# RS232.net
KiCad netlist of a schematic drawn in EAGLE
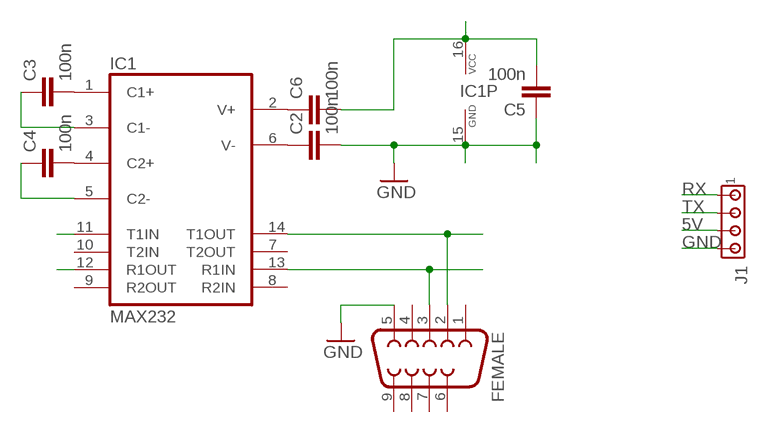
[diagram p0: schematic, sheet 1]

(export (version "E")
  (design (tool "Eeschema 10.0.6"))
  (components
    (comp (ref "C2")
      (value "100n")
      (footprint "eagle-import:C0805")
      (libsource (lib "eagle-import") (part "C-EUC0805"))
    )
    (comp (ref "C3")
      (value "100n")
      (footprint "eagle-import:C0805")
      (libsource (lib "eagle-import") (part "C-EUC0805"))
    )
    (comp (ref "C4")
      (value "100n")
      (footprint "eagle-import:C0805")
      (libsource (lib "eagle-import") (part "C-EUC0805"))
    )
    (comp (ref "C5")
      (value "100n")
      (footprint "eagle-import:C0805")
      (libsource (lib "eagle-import") (part "C-EUC0805"))
    )
    (comp (ref "C6")
      (value "100n")
      (footprint "eagle-import:C0805")
      (libsource (lib "eagle-import") (part "C-EUC0805"))
    )
    (comp (ref "FEMALE")
      (value "F09H")
      (footprint "eagle-import:F09H")
      (libsource (lib "eagle-import") (part "F09H"))
    )
    (comp (ref "IC1")
      (value "MAX232")
      (footprint "eagle-import:SO16")
      (libsource (lib "eagle-import") (part "MAX232ECWES"))
    )
    (comp (ref "J1")
      (value "MTA04-156")
      (footprint "eagle-import:1X4MTA")
      (libsource (lib "eagle-import") (part "MTA04-156"))
    )
  )
  (nets
    (net (code "1") (name "/5V") (class "Default")
      (node (ref "C5") (pin "2") (pinfunction "2_2") (pintype "passive"))
      (node (ref "C6") (pin "2") (pinfunction "2_2") (pintype "passive"))
      (node (ref "IC1") (pin "16") (pinfunction "VCC_16") (pintype "power_in"))
      (node (ref "J1") (pin "3") (pinfunction "3_3") (pintype "passive"))
    )
    (net (code "2") (name "/RX") (class "Default")
      (node (ref "IC1") (pin "12") (pinfunction "R1OUT_12") (pintype "output"))
      (node (ref "J1") (pin "1") (pinfunction "1_1") (pintype "passive"))
    )
    (net (code "3") (name "/TX") (class "Default")
      (node (ref "IC1") (pin "11") (pinfunction "T1IN_11") (pintype "input"))
      (node (ref "J1") (pin "2") (pinfunction "2_2") (pintype "passive"))
    )
    (net (code "4") (name "GND") (class "Default")
      (node (ref "C2") (pin "2") (pinfunction "2_2") (pintype "passive"))
      (node (ref "C5") (pin "1") (pinfunction "1_1") (pintype "passive"))
      (node (ref "FEMALE") (pin "5") (pinfunction "5_5") (pintype "passive"))
      (node (ref "IC1") (pin "15") (pinfunction "GND_15") (pintype "power_in"))
      (node (ref "J1") (pin "4") (pinfunction "4_4") (pintype "passive"))
    )
    (net (code "5") (name "Net-(IC1A-C1+)") (class "Default")
      (node (ref "C3") (pin "2") (pinfunction "2_2") (pintype "passive"))
      (node (ref "IC1") (pin "1") (pinfunction "C1+_1") (pintype "bidirectional"))
    )
    (net (code "6") (name "Net-(IC1A-C1-)") (class "Default")
      (node (ref "C3") (pin "1") (pinfunction "1_1") (pintype "passive"))
      (node (ref "IC1") (pin "3") (pinfunction "C1-_3") (pintype "bidirectional"))
    )
    (net (code "7") (name "Net-(IC1A-C2+)") (class "Default")
      (node (ref "C4") (pin "2") (pinfunction "2_2") (pintype "passive"))
      (node (ref "IC1") (pin "4") (pinfunction "C2+_4") (pintype "bidirectional"))
    )
    (net (code "8") (name "Net-(IC1A-C2-)") (class "Default")
      (node (ref "C4") (pin "1") (pinfunction "1_1") (pintype "passive"))
      (node (ref "IC1") (pin "5") (pinfunction "C2-_5") (pintype "bidirectional"))
    )
    (net (code "9") (name "Net-(IC1A-R1IN)") (class "Default")
      (node (ref "FEMALE") (pin "3") (pinfunction "3_3") (pintype "passive"))
      (node (ref "IC1") (pin "13") (pinfunction "R1IN_13") (pintype "input"))
    )
    (net (code "10") (name "Net-(IC1A-T1OUT)") (class "Default")
      (node (ref "FEMALE") (pin "2") (pinfunction "2_2") (pintype "passive"))
      (node (ref "IC1") (pin "14") (pinfunction "T1OUT_14") (pintype "output"))
    )
    (net (code "11") (name "Net-(IC1A-V+)") (class "Default")
      (node (ref "C6") (pin "1") (pinfunction "1_1") (pintype "passive"))
      (node (ref "IC1") (pin "2") (pinfunction "V+_2") (pintype "bidirectional"))
    )
    (net (code "12") (name "Net-(IC1A-V-)") (class "Default")
      (node (ref "C2") (pin "1") (pinfunction "1_1") (pintype "passive"))
      (node (ref "IC1") (pin "6") (pinfunction "V-_6") (pintype "bidirectional"))
    )
    (net (code "13") (name "unconnected-(FEMALE-Pad1)") (class "Default")
      (node (ref "FEMALE") (pin "1") (pinfunction "1_1") (pintype "passive"))
    )
    (net (code "14") (name "unconnected-(FEMALE-Pad4)") (class "Default")
      (node (ref "FEMALE") (pin "4") (pinfunction "4_4") (pintype "passive"))
    )
    (net (code "15") (name "unconnected-(FEMALE-Pad6)") (class "Default")
      (node (ref "FEMALE") (pin "6") (pinfunction "6_6") (pintype "passive"))
    )
    (net (code "16") (name "unconnected-(FEMALE-Pad7)") (class "Default")
      (node (ref "FEMALE") (pin "7") (pinfunction "7_7") (pintype "passive"))
    )
    (net (code "17") (name "unconnected-(FEMALE-Pad8)") (class "Default")
      (node (ref "FEMALE") (pin "8") (pinfunction "8_8") (pintype "passive"))
    )
    (net (code "18") (name "unconnected-(FEMALE-Pad9)") (class "Default")
      (node (ref "FEMALE") (pin "9") (pinfunction "9_9") (pintype "passive"))
    )
    (net (code "19") (name "unconnected-(IC1A-R2IN-Pad8)") (class "Default")
      (node (ref "IC1") (pin "8") (pinfunction "R2IN_8") (pintype "input"))
    )
    (net (code "20") (name "unconnected-(IC1A-R2OUT-Pad9)") (class "Default")
      (node (ref "IC1") (pin "9") (pinfunction "R2OUT_9") (pintype "output"))
    )
    (net (code "21") (name "unconnected-(IC1A-T2IN-Pad10)") (class "Default")
      (node (ref "IC1") (pin "10") (pinfunction "T2IN_10") (pintype "input"))
    )
    (net (code "22") (name "unconnected-(IC1A-T2OUT-Pad7)") (class "Default")
      (node (ref "IC1") (pin "7") (pinfunction "T2OUT_7") (pintype "output"))
    )
  )
)
